# M216B.net
KiCad netlist of a schematic drawn in EAGLE
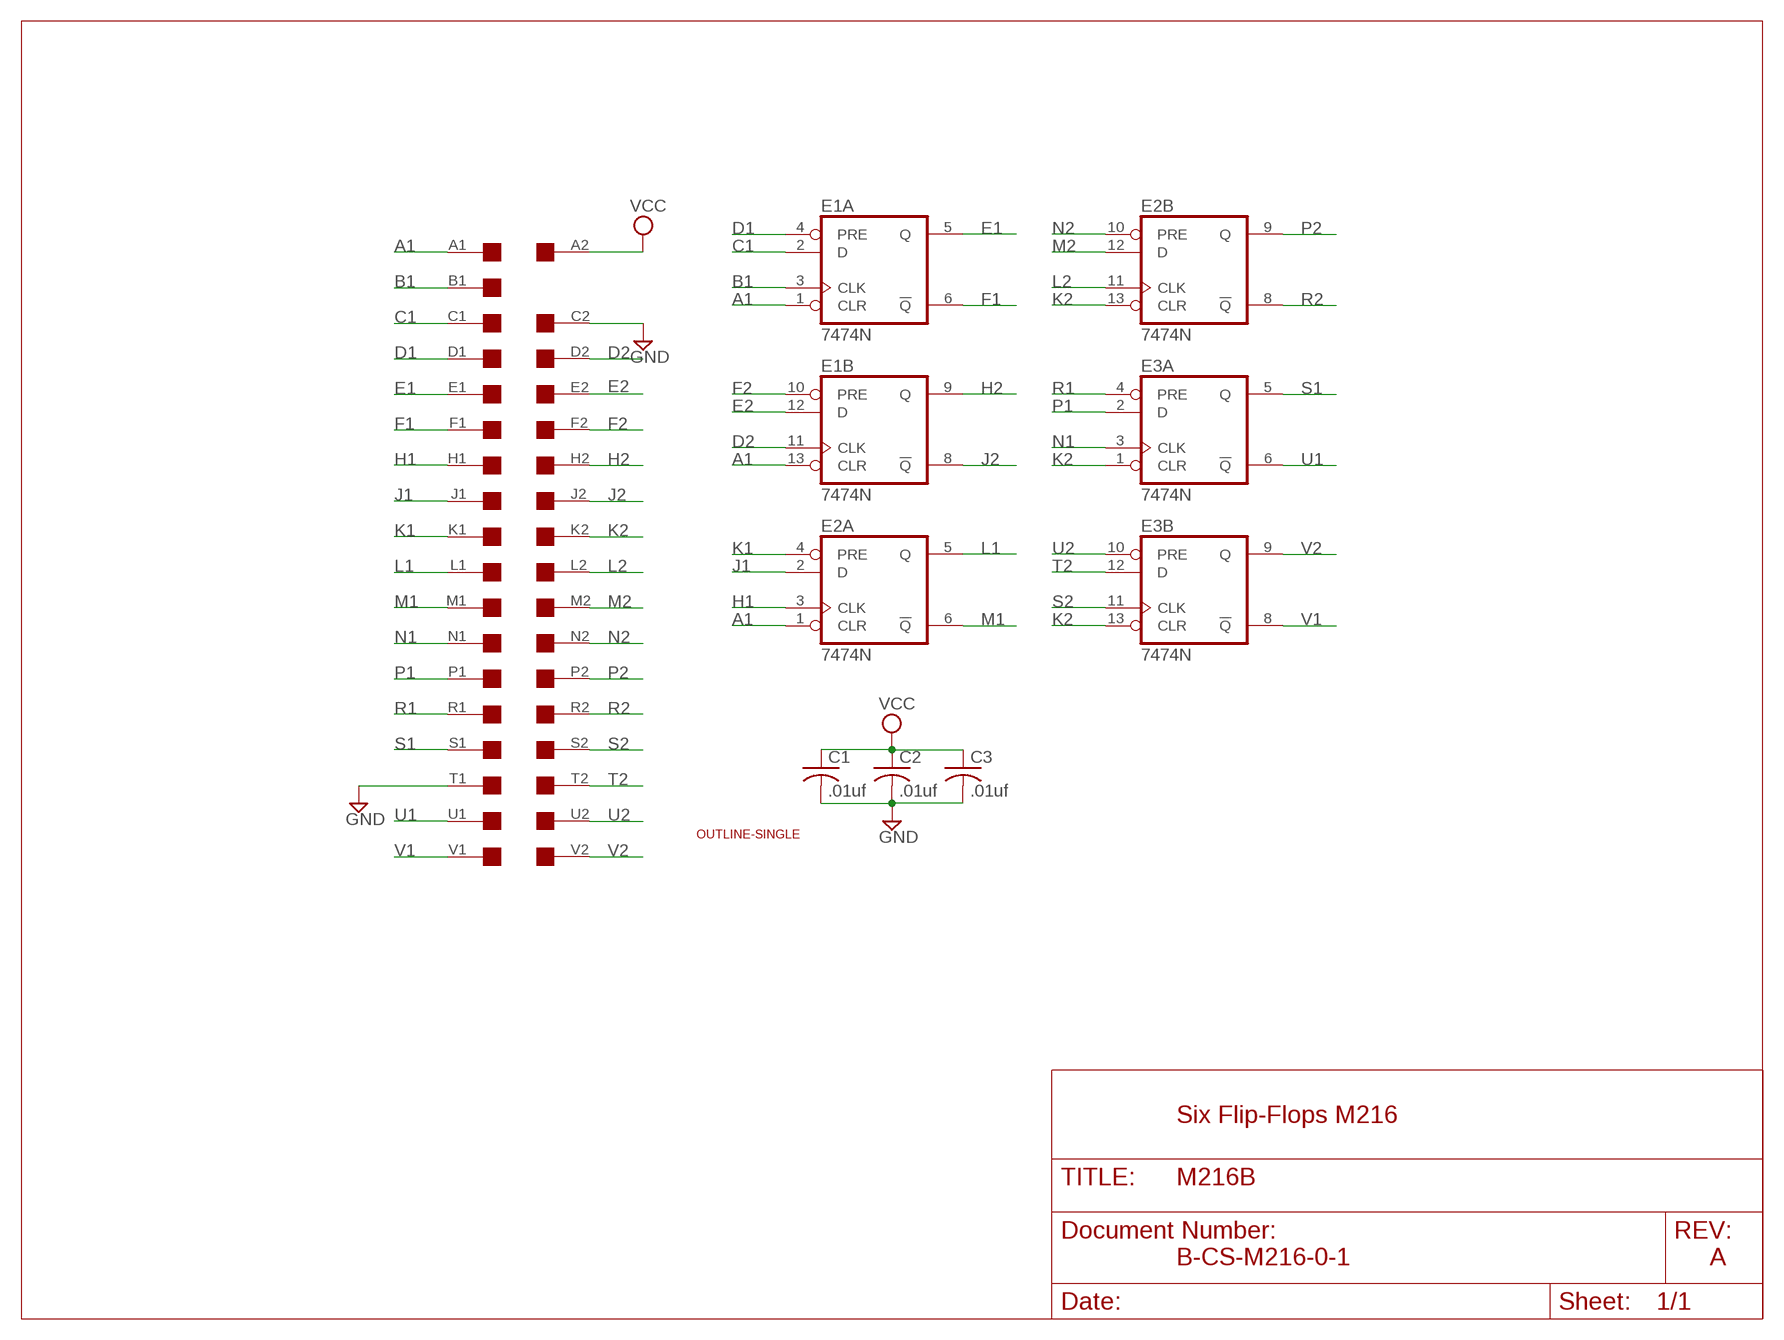
[diagram p0: schematic, sheet 1]

(export (version "E")
  (design (tool "Eeschema 10.0.6"))
  (components
    (comp (ref "C1")
      (value ".01uf")
      (footprint "eagle-import:C050-025X075")
      (libsource (lib "eagle-import") (part "C-US050-025X075"))
    )
    (comp (ref "C2")
      (value ".01uf")
      (footprint "eagle-import:C050-025X075")
      (libsource (lib "eagle-import") (part "C-US050-025X075"))
    )
    (comp (ref "C3")
      (value ".01uf")
      (footprint "eagle-import:C050-025X075")
      (libsource (lib "eagle-import") (part "C-US050-025X075"))
    )
    (comp (ref "E1")
      (value "7474N")
      (footprint "eagle-import:DIL14")
      (libsource (lib "eagle-import") (part "7474NS"))
    )
    (comp (ref "E2")
      (value "7474N")
      (footprint "eagle-import:DIL14")
      (libsource (lib "eagle-import") (part "7474NS"))
    )
    (comp (ref "E3")
      (value "7474N")
      (footprint "eagle-import:DIL14")
      (libsource (lib "eagle-import") (part "7474NS"))
    )
    (comp (ref "U$1")
      (value "OUTLINE-SINGLE")
      (footprint "eagle-import:SINGLE")
      (libsource (lib "eagle-import") (part "OUTLINE-SINGLE"))
    )
    (comp (ref "U$4")
      (value "SINGLE")
      (footprint "eagle-import:EDGE-CON2")
      (libsource (lib "eagle-import") (part "SINGLE"))
    )
  )
  (nets
    (net (code "1") (name "/A1") (class "Default")
      (node (ref "E1") (pin "1") (pinfunction "CLR_1") (pintype "input"))
      (node (ref "E1") (pin "13") (pinfunction "CLR_13") (pintype "input"))
      (node (ref "E2") (pin "1") (pinfunction "CLR_1") (pintype "input"))
      (node (ref "U$4") (pin "A1") (pinfunction "1_A1") (pintype "bidirectional"))
    )
    (net (code "2") (name "/B1") (class "Default")
      (node (ref "E1") (pin "3") (pinfunction "CLK_3") (pintype "input"))
      (node (ref "U$4") (pin "B1") (pinfunction "1_B1") (pintype "bidirectional"))
    )
    (net (code "3") (name "/C1") (class "Default")
      (node (ref "E1") (pin "2") (pinfunction "D_2") (pintype "input"))
      (node (ref "U$4") (pin "C1") (pinfunction "1_C1") (pintype "bidirectional"))
    )
    (net (code "4") (name "/D1") (class "Default")
      (node (ref "E1") (pin "4") (pinfunction "PRE_4") (pintype "input"))
      (node (ref "U$4") (pin "D1") (pinfunction "1_D1") (pintype "bidirectional"))
    )
    (net (code "5") (name "/D2") (class "Default")
      (node (ref "E1") (pin "11") (pinfunction "CLK_11") (pintype "input"))
      (node (ref "U$4") (pin "D2") (pinfunction "1_D2") (pintype "bidirectional"))
    )
    (net (code "6") (name "/E1") (class "Default")
      (node (ref "E1") (pin "5") (pinfunction "Q_5") (pintype "output"))
      (node (ref "U$4") (pin "E1") (pinfunction "1_E1") (pintype "bidirectional"))
    )
    (net (code "7") (name "/E2") (class "Default")
      (node (ref "E1") (pin "12") (pinfunction "D_12") (pintype "input"))
      (node (ref "U$4") (pin "E2") (pinfunction "1_E2") (pintype "bidirectional"))
    )
    (net (code "8") (name "/F1") (class "Default")
      (node (ref "E1") (pin "6") (pinfunction "~{Q}_6") (pintype "output"))
      (node (ref "U$4") (pin "F1") (pinfunction "1_F1") (pintype "bidirectional"))
    )
    (net (code "9") (name "/F2") (class "Default")
      (node (ref "E1") (pin "10") (pinfunction "PRE_10") (pintype "input"))
      (node (ref "U$4") (pin "F2") (pinfunction "1_F2") (pintype "bidirectional"))
    )
    (net (code "10") (name "/H1") (class "Default")
      (node (ref "E2") (pin "3") (pinfunction "CLK_3") (pintype "input"))
      (node (ref "U$4") (pin "H1") (pinfunction "1_H1") (pintype "bidirectional"))
    )
    (net (code "11") (name "/H2") (class "Default")
      (node (ref "E1") (pin "9") (pinfunction "Q_9") (pintype "output"))
      (node (ref "U$4") (pin "H2") (pinfunction "1_H2") (pintype "bidirectional"))
    )
    (net (code "12") (name "/J1") (class "Default")
      (node (ref "E2") (pin "2") (pinfunction "D_2") (pintype "input"))
      (node (ref "U$4") (pin "J1") (pinfunction "1_J1") (pintype "bidirectional"))
    )
    (net (code "13") (name "/J2") (class "Default")
      (node (ref "E1") (pin "8") (pinfunction "~{Q}_8") (pintype "output"))
      (node (ref "U$4") (pin "J2") (pinfunction "1_J2") (pintype "bidirectional"))
    )
    (net (code "14") (name "/K1") (class "Default")
      (node (ref "E2") (pin "4") (pinfunction "PRE_4") (pintype "input"))
      (node (ref "U$4") (pin "K1") (pinfunction "1_K1") (pintype "bidirectional"))
    )
    (net (code "15") (name "/K2") (class "Default")
      (node (ref "E2") (pin "13") (pinfunction "CLR_13") (pintype "input"))
      (node (ref "E3") (pin "1") (pinfunction "CLR_1") (pintype "input"))
      (node (ref "E3") (pin "13") (pinfunction "CLR_13") (pintype "input"))
      (node (ref "U$4") (pin "K2") (pinfunction "1_K2") (pintype "bidirectional"))
    )
    (net (code "16") (name "/L1") (class "Default")
      (node (ref "E2") (pin "5") (pinfunction "Q_5") (pintype "output"))
      (node (ref "U$4") (pin "L1") (pinfunction "1_L1") (pintype "bidirectional"))
    )
    (net (code "17") (name "/L2") (class "Default")
      (node (ref "E2") (pin "11") (pinfunction "CLK_11") (pintype "input"))
      (node (ref "U$4") (pin "L2") (pinfunction "1_L2") (pintype "bidirectional"))
    )
    (net (code "18") (name "/M1") (class "Default")
      (node (ref "E2") (pin "6") (pinfunction "~{Q}_6") (pintype "output"))
      (node (ref "U$4") (pin "M1") (pinfunction "1_M1") (pintype "bidirectional"))
    )
    (net (code "19") (name "/M2") (class "Default")
      (node (ref "E2") (pin "12") (pinfunction "D_12") (pintype "input"))
      (node (ref "U$4") (pin "M2") (pinfunction "1_M2") (pintype "bidirectional"))
    )
    (net (code "20") (name "/N1") (class "Default")
      (node (ref "E3") (pin "3") (pinfunction "CLK_3") (pintype "input"))
      (node (ref "U$4") (pin "N1") (pinfunction "1_N1") (pintype "bidirectional"))
    )
    (net (code "21") (name "/N2") (class "Default")
      (node (ref "E2") (pin "10") (pinfunction "PRE_10") (pintype "input"))
      (node (ref "U$4") (pin "N2") (pinfunction "1_N2") (pintype "bidirectional"))
    )
    (net (code "22") (name "/P1") (class "Default")
      (node (ref "E3") (pin "2") (pinfunction "D_2") (pintype "input"))
      (node (ref "U$4") (pin "P1") (pinfunction "1_P1") (pintype "bidirectional"))
    )
    (net (code "23") (name "/P2") (class "Default")
      (node (ref "E2") (pin "9") (pinfunction "Q_9") (pintype "output"))
      (node (ref "U$4") (pin "P2") (pinfunction "1_P2") (pintype "bidirectional"))
    )
    (net (code "24") (name "/R1") (class "Default")
      (node (ref "E3") (pin "4") (pinfunction "PRE_4") (pintype "input"))
      (node (ref "U$4") (pin "R1") (pinfunction "1_R1") (pintype "bidirectional"))
    )
    (net (code "25") (name "/R2") (class "Default")
      (node (ref "E2") (pin "8") (pinfunction "~{Q}_8") (pintype "output"))
      (node (ref "U$4") (pin "R2") (pinfunction "1_R2") (pintype "bidirectional"))
    )
    (net (code "26") (name "/S1") (class "Default")
      (node (ref "E3") (pin "5") (pinfunction "Q_5") (pintype "output"))
      (node (ref "U$4") (pin "S1") (pinfunction "1_S1") (pintype "bidirectional"))
    )
    (net (code "27") (name "/S2") (class "Default")
      (node (ref "E3") (pin "11") (pinfunction "CLK_11") (pintype "input"))
      (node (ref "U$4") (pin "S2") (pinfunction "1_S2") (pintype "bidirectional"))
    )
    (net (code "28") (name "/T2") (class "Default")
      (node (ref "E3") (pin "12") (pinfunction "D_12") (pintype "input"))
      (node (ref "U$4") (pin "T2") (pinfunction "1_T2") (pintype "bidirectional"))
    )
    (net (code "29") (name "/U1") (class "Default")
      (node (ref "E3") (pin "6") (pinfunction "~{Q}_6") (pintype "output"))
      (node (ref "U$4") (pin "U1") (pinfunction "1_U1") (pintype "bidirectional"))
    )
    (net (code "30") (name "/U2") (class "Default")
      (node (ref "E3") (pin "10") (pinfunction "PRE_10") (pintype "input"))
      (node (ref "U$4") (pin "U2") (pinfunction "1_U2") (pintype "bidirectional"))
    )
    (net (code "31") (name "/V1") (class "Default")
      (node (ref "E3") (pin "8") (pinfunction "~{Q}_8") (pintype "output"))
      (node (ref "U$4") (pin "V1") (pinfunction "1_V1") (pintype "bidirectional"))
    )
    (net (code "32") (name "/V2") (class "Default")
      (node (ref "E3") (pin "9") (pinfunction "Q_9") (pintype "output"))
      (node (ref "U$4") (pin "V2") (pinfunction "1_V2") (pintype "bidirectional"))
    )
    (net (code "33") (name "GND") (class "Default")
      (node (ref "C1") (pin "2") (pinfunction "2_2") (pintype "passive"))
      (node (ref "C2") (pin "2") (pinfunction "2_2") (pintype "passive"))
      (node (ref "C3") (pin "2") (pinfunction "2_2") (pintype "passive"))
      (node (ref "U$4") (pin "C2") (pinfunction "1_C2") (pintype "bidirectional"))
      (node (ref "U$4") (pin "T1") (pinfunction "1_T1") (pintype "bidirectional"))
    )
    (net (code "34") (name "VCC") (class "Default")
      (node (ref "C1") (pin "1") (pinfunction "1_1") (pintype "passive"))
      (node (ref "C2") (pin "1") (pinfunction "1_1") (pintype "passive"))
      (node (ref "C3") (pin "1") (pinfunction "1_1") (pintype "passive"))
      (node (ref "U$4") (pin "A2") (pinfunction "1_A2") (pintype "bidirectional"))
    )
  )
)
